# stepper_driver1_c.net
KiCad netlist of a schematic drawn in EAGLE
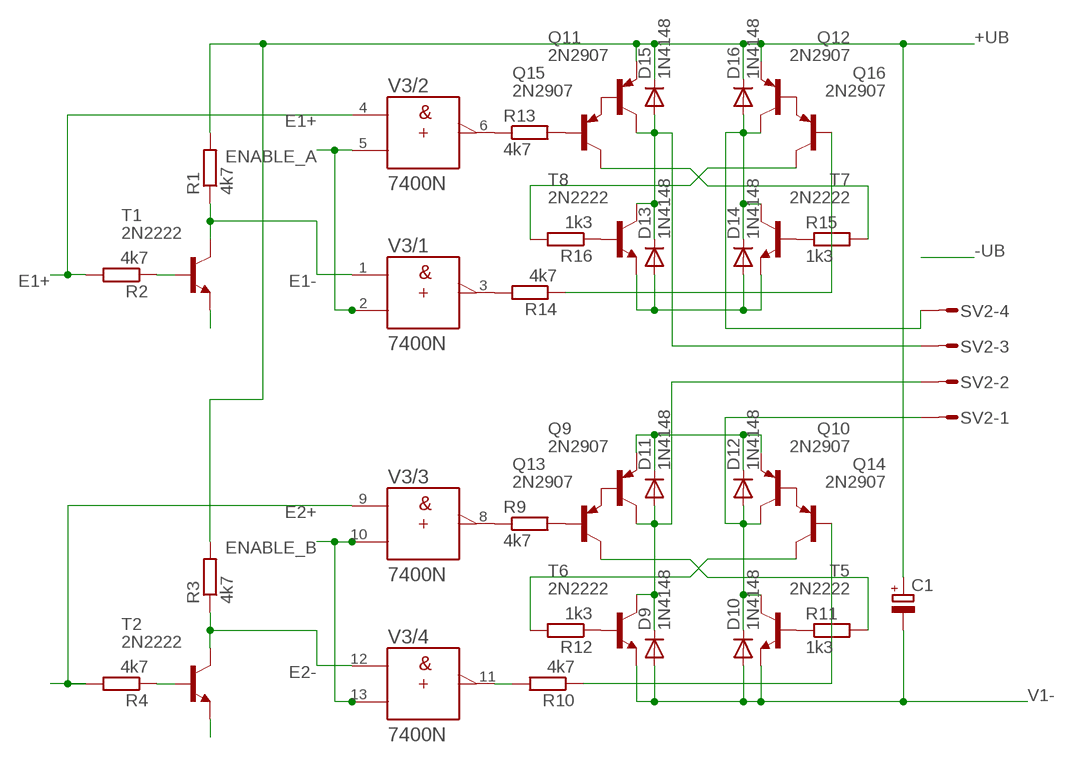
[diagram p0: schematic, sheet 1]

(export (version "E")
  (design (tool "Eeschema 10.0.6"))
  (components
    (comp (ref "C1")
      (value "CPOL-EUE3.5-10")
      (footprint "eagle-import:E3,5-10")
      (libsource (lib "eagle-import") (part "CPOL-EUE3.5-10"))
    )
    (comp (ref "D9")
      (value "1N4148")
      (footprint "eagle-import:D-2.5")
      (libsource (lib "eagle-import") (part "DIODE-D-2.5"))
    )
    (comp (ref "D10")
      (value "1N4148")
      (footprint "eagle-import:D-2.5")
      (libsource (lib "eagle-import") (part "DIODE-D-2.5"))
    )
    (comp (ref "D11")
      (value "1N4148")
      (footprint "eagle-import:D-2.5")
      (libsource (lib "eagle-import") (part "DIODE-D-2.5"))
    )
    (comp (ref "D12")
      (value "1N4148")
      (footprint "eagle-import:D-2.5")
      (libsource (lib "eagle-import") (part "DIODE-D-2.5"))
    )
    (comp (ref "D13")
      (value "1N4148")
      (footprint "eagle-import:D-2.5")
      (libsource (lib "eagle-import") (part "DIODE-D-2.5"))
    )
    (comp (ref "D14")
      (value "1N4148")
      (footprint "eagle-import:D-2.5")
      (libsource (lib "eagle-import") (part "DIODE-D-2.5"))
    )
    (comp (ref "D15")
      (value "1N4148")
      (footprint "eagle-import:D-2.5")
      (libsource (lib "eagle-import") (part "DIODE-D-2.5"))
    )
    (comp (ref "D16")
      (value "1N4148")
      (footprint "eagle-import:D-2.5")
      (libsource (lib "eagle-import") (part "DIODE-D-2.5"))
    )
    (comp (ref "Q9")
      (value "2N2907")
      (footprint "eagle-import:TO18")
      (libsource (lib "eagle-import") (part "2N2907"))
    )
    (comp (ref "Q10")
      (value "2N2907")
      (footprint "eagle-import:TO18")
      (libsource (lib "eagle-import") (part "2N2907"))
    )
    (comp (ref "Q11")
      (value "2N2907")
      (footprint "eagle-import:TO18")
      (libsource (lib "eagle-import") (part "2N2907"))
    )
    (comp (ref "Q12")
      (value "2N2907")
      (footprint "eagle-import:TO18")
      (libsource (lib "eagle-import") (part "2N2907"))
    )
    (comp (ref "Q13")
      (value "2N2907")
      (footprint "eagle-import:TO18")
      (libsource (lib "eagle-import") (part "2N2907"))
    )
    (comp (ref "Q14")
      (value "2N2907")
      (footprint "eagle-import:TO18")
      (libsource (lib "eagle-import") (part "2N2907"))
    )
    (comp (ref "Q15")
      (value "2N2907")
      (footprint "eagle-import:TO18")
      (libsource (lib "eagle-import") (part "2N2907"))
    )
    (comp (ref "Q16")
      (value "2N2907")
      (footprint "eagle-import:TO18")
      (libsource (lib "eagle-import") (part "2N2907"))
    )
    (comp (ref "R1")
      (value "4k7")
      (footprint "eagle-import:0207_10")
      (libsource (lib "eagle-import") (part "R-EU_0207/10"))
    )
    (comp (ref "R2")
      (value "4k7")
      (footprint "eagle-import:0207_10")
      (libsource (lib "eagle-import") (part "R-EU_0207/10"))
    )
    (comp (ref "R3")
      (value "4k7")
      (footprint "eagle-import:0207_10")
      (libsource (lib "eagle-import") (part "R-EU_0207/10"))
    )
    (comp (ref "R4")
      (value "4k7")
      (footprint "eagle-import:0207_10")
      (libsource (lib "eagle-import") (part "R-EU_0207/10"))
    )
    (comp (ref "R9")
      (value "4k7")
      (footprint "eagle-import:0207_10")
      (libsource (lib "eagle-import") (part "R-EU_0207/10"))
    )
    (comp (ref "R10")
      (value "4k7")
      (footprint "eagle-import:0207_12")
      (libsource (lib "eagle-import") (part "R-EU_0207/12"))
    )
    (comp (ref "R11")
      (value "1k3")
      (footprint "eagle-import:0207_10")
      (libsource (lib "eagle-import") (part "R-EU_0207/10"))
    )
    (comp (ref "R12")
      (value "1k3")
      (footprint "eagle-import:0207_10")
      (libsource (lib "eagle-import") (part "R-EU_0207/10"))
    )
    (comp (ref "R13")
      (value "4k7")
      (footprint "eagle-import:0207_10")
      (libsource (lib "eagle-import") (part "R-EU_0207/10"))
    )
    (comp (ref "R14")
      (value "4k7")
      (footprint "eagle-import:0207_10")
      (libsource (lib "eagle-import") (part "R-EU_0207/10"))
    )
    (comp (ref "R15")
      (value "1k3")
      (footprint "eagle-import:0207_10")
      (libsource (lib "eagle-import") (part "R-EU_0207/10"))
    )
    (comp (ref "R16")
      (value "1k3")
      (footprint "eagle-import:0207_10")
      (libsource (lib "eagle-import") (part "R-EU_0207/10"))
    )
    (comp (ref "SV2")
      (value "S04P")
      (footprint "eagle-import:S04P")
      (libsource (lib "eagle-import") (part "S04P"))
    )
    (comp (ref "T1")
      (value "2N2222")
      (footprint "eagle-import:TO18")
      (libsource (lib "eagle-import") (part "2N2222"))
    )
    (comp (ref "T2")
      (value "2N2222")
      (footprint "eagle-import:TO18")
      (libsource (lib "eagle-import") (part "2N2222"))
    )
    (comp (ref "T5")
      (value "2N2222")
      (footprint "eagle-import:TO18")
      (libsource (lib "eagle-import") (part "2N2222"))
    )
    (comp (ref "T6")
      (value "2N2222")
      (footprint "eagle-import:TO18")
      (libsource (lib "eagle-import") (part "2N2222"))
    )
    (comp (ref "T7")
      (value "2N2222")
      (footprint "eagle-import:TO18")
      (libsource (lib "eagle-import") (part "2N2222"))
    )
    (comp (ref "T8")
      (value "2N2222")
      (footprint "eagle-import:TO18")
      (libsource (lib "eagle-import") (part "2N2222"))
    )
    (comp (ref "V3")
      (value "7400N")
      (footprint "eagle-import:DIL14")
      (libsource (lib "eagle-import") (part "7400N"))
    )
  )
  (nets
    (net (code "1") (name "/+UB") (class "Default")
      (node (ref "C1") (pin "+") (pinfunction "+_+") (pintype "passive"))
      (node (ref "D11") (pin "C") (pinfunction "C_C") (pintype "passive"))
      (node (ref "D12") (pin "C") (pinfunction "C_C") (pintype "passive"))
      (node (ref "D15") (pin "C") (pinfunction "C_C") (pintype "passive"))
      (node (ref "D16") (pin "C") (pinfunction "C_C") (pintype "passive"))
      (node (ref "Q10") (pin "1") (pinfunction "E_1") (pintype "passive"))
      (node (ref "Q11") (pin "1") (pinfunction "E_1") (pintype "passive"))
      (node (ref "Q12") (pin "1") (pinfunction "E_1") (pintype "passive"))
      (node (ref "Q9") (pin "1") (pinfunction "E_1") (pintype "passive"))
      (node (ref "R1") (pin "2") (pinfunction "2_2") (pintype "passive"))
      (node (ref "R3") (pin "2") (pinfunction "2_2") (pintype "passive"))
    )
    (net (code "2") (name "/-UB") (class "Default")
      (node (ref "T1") (pin "1") (pinfunction "E_1") (pintype "passive"))
      (node (ref "T2") (pin "1") (pinfunction "E_1") (pintype "passive"))
    )
    (net (code "3") (name "/E1+") (class "Default")
      (node (ref "R2") (pin "2") (pinfunction "2_2") (pintype "passive"))
      (node (ref "V3") (pin "4") (pinfunction "A_4") (pintype "input"))
    )
    (net (code "4") (name "/E1-") (class "Default")
      (node (ref "R1") (pin "1") (pinfunction "1_1") (pintype "passive"))
      (node (ref "T1") (pin "3") (pinfunction "C_3") (pintype "passive"))
      (node (ref "V3") (pin "1") (pinfunction "A_1") (pintype "input"))
    )
    (net (code "5") (name "/E2+") (class "Default")
      (node (ref "R4") (pin "2") (pinfunction "2_2") (pintype "passive"))
      (node (ref "V3") (pin "9") (pinfunction "A_9") (pintype "input"))
    )
    (net (code "6") (name "/E2-") (class "Default")
      (node (ref "R3") (pin "1") (pinfunction "1_1") (pintype "passive"))
      (node (ref "T2") (pin "3") (pinfunction "C_3") (pintype "passive"))
      (node (ref "V3") (pin "12") (pinfunction "A_12") (pintype "input"))
    )
    (net (code "7") (name "/ENABLE_A") (class "Default")
      (node (ref "V3") (pin "2") (pinfunction "B_2") (pintype "input"))
      (node (ref "V3") (pin "5") (pinfunction "B_5") (pintype "input"))
    )
    (net (code "8") (name "/ENABLE_B") (class "Default")
      (node (ref "V3") (pin "10") (pinfunction "B_10") (pintype "input"))
      (node (ref "V3") (pin "13") (pinfunction "B_13") (pintype "input"))
    )
    (net (code "9") (name "/V1-") (class "Default")
      (node (ref "C1") (pin "-") (pinfunction "-_-") (pintype "passive"))
      (node (ref "D10") (pin "A") (pinfunction "A_A") (pintype "passive"))
      (node (ref "D13") (pin "A") (pinfunction "A_A") (pintype "passive"))
      (node (ref "D14") (pin "A") (pinfunction "A_A") (pintype "passive"))
      (node (ref "D9") (pin "A") (pinfunction "A_A") (pintype "passive"))
      (node (ref "T5") (pin "1") (pinfunction "E_1") (pintype "passive"))
      (node (ref "T6") (pin "1") (pinfunction "E_1") (pintype "passive"))
      (node (ref "T7") (pin "1") (pinfunction "E_1") (pintype "passive"))
      (node (ref "T8") (pin "1") (pinfunction "E_1") (pintype "passive"))
    )
    (net (code "10") (name "Net-(Q9-C)") (class "Default")
      (node (ref "D11") (pin "A") (pinfunction "A_A") (pintype "passive"))
      (node (ref "D9") (pin "C") (pinfunction "C_C") (pintype "passive"))
      (node (ref "Q9") (pin "3") (pinfunction "C_3") (pintype "passive"))
      (node (ref "SV2") (pin "2") (pinfunction "S_2") (pintype "passive"))
      (node (ref "T6") (pin "3") (pinfunction "C_3") (pintype "passive"))
    )
    (net (code "11") (name "Net-(Q10-B)") (class "Default")
      (node (ref "Q10") (pin "2") (pinfunction "B_2") (pintype "passive"))
      (node (ref "Q14") (pin "1") (pinfunction "E_1") (pintype "passive"))
    )
    (net (code "12") (name "Net-(Q10-C)") (class "Default")
      (node (ref "D10") (pin "C") (pinfunction "C_C") (pintype "passive"))
      (node (ref "D12") (pin "A") (pinfunction "A_A") (pintype "passive"))
      (node (ref "Q10") (pin "3") (pinfunction "C_3") (pintype "passive"))
      (node (ref "SV2") (pin "1") (pinfunction "S_1") (pintype "passive"))
      (node (ref "T5") (pin "3") (pinfunction "C_3") (pintype "passive"))
    )
    (net (code "13") (name "Net-(Q11-B)") (class "Default")
      (node (ref "Q11") (pin "2") (pinfunction "B_2") (pintype "passive"))
      (node (ref "Q15") (pin "1") (pinfunction "E_1") (pintype "passive"))
    )
    (net (code "14") (name "Net-(Q11-C)") (class "Default")
      (node (ref "D13") (pin "C") (pinfunction "C_C") (pintype "passive"))
      (node (ref "D15") (pin "A") (pinfunction "A_A") (pintype "passive"))
      (node (ref "Q11") (pin "3") (pinfunction "C_3") (pintype "passive"))
      (node (ref "SV2") (pin "3") (pinfunction "S_3") (pintype "passive"))
      (node (ref "T8") (pin "3") (pinfunction "C_3") (pintype "passive"))
    )
    (net (code "15") (name "Net-(Q12-B)") (class "Default")
      (node (ref "Q12") (pin "2") (pinfunction "B_2") (pintype "passive"))
      (node (ref "Q16") (pin "1") (pinfunction "E_1") (pintype "passive"))
    )
    (net (code "16") (name "Net-(Q12-C)") (class "Default")
      (node (ref "D14") (pin "C") (pinfunction "C_C") (pintype "passive"))
      (node (ref "D16") (pin "A") (pinfunction "A_A") (pintype "passive"))
      (node (ref "Q12") (pin "3") (pinfunction "C_3") (pintype "passive"))
      (node (ref "SV2") (pin "4") (pinfunction "S_4") (pintype "passive"))
      (node (ref "T7") (pin "3") (pinfunction "C_3") (pintype "passive"))
    )
    (net (code "17") (name "Net-(Q13-B)") (class "Default")
      (node (ref "Q13") (pin "2") (pinfunction "B_2") (pintype "passive"))
      (node (ref "R9") (pin "2") (pinfunction "2_2") (pintype "passive"))
    )
    (net (code "18") (name "Net-(Q13-C)") (class "Default")
      (node (ref "Q13") (pin "3") (pinfunction "C_3") (pintype "passive"))
      (node (ref "R11") (pin "2") (pinfunction "2_2") (pintype "passive"))
    )
    (net (code "19") (name "Net-(Q13-E)") (class "Default")
      (node (ref "Q13") (pin "1") (pinfunction "E_1") (pintype "passive"))
      (node (ref "Q9") (pin "2") (pinfunction "B_2") (pintype "passive"))
    )
    (net (code "20") (name "Net-(Q14-B)") (class "Default")
      (node (ref "Q14") (pin "2") (pinfunction "B_2") (pintype "passive"))
      (node (ref "R10") (pin "1") (pinfunction "1_1") (pintype "passive"))
    )
    (net (code "21") (name "Net-(Q14-C)") (class "Default")
      (node (ref "Q14") (pin "3") (pinfunction "C_3") (pintype "passive"))
      (node (ref "R12") (pin "2") (pinfunction "2_2") (pintype "passive"))
    )
    (net (code "22") (name "Net-(Q15-B)") (class "Default")
      (node (ref "Q15") (pin "2") (pinfunction "B_2") (pintype "passive"))
      (node (ref "R13") (pin "2") (pinfunction "2_2") (pintype "passive"))
    )
    (net (code "23") (name "Net-(Q15-C)") (class "Default")
      (node (ref "Q15") (pin "3") (pinfunction "C_3") (pintype "passive"))
      (node (ref "R15") (pin "2") (pinfunction "2_2") (pintype "passive"))
    )
    (net (code "24") (name "Net-(Q16-B)") (class "Default")
      (node (ref "Q16") (pin "2") (pinfunction "B_2") (pintype "passive"))
      (node (ref "R14") (pin "1") (pinfunction "1_1") (pintype "passive"))
    )
    (net (code "25") (name "Net-(Q16-C)") (class "Default")
      (node (ref "Q16") (pin "3") (pinfunction "C_3") (pintype "passive"))
      (node (ref "R16") (pin "2") (pinfunction "2_2") (pintype "passive"))
    )
    (net (code "26") (name "Net-(T1-B)") (class "Default")
      (node (ref "R2") (pin "1") (pinfunction "1_1") (pintype "passive"))
      (node (ref "T1") (pin "2") (pinfunction "B_2") (pintype "passive"))
    )
    (net (code "27") (name "Net-(T2-B)") (class "Default")
      (node (ref "R4") (pin "1") (pinfunction "1_1") (pintype "passive"))
      (node (ref "T2") (pin "2") (pinfunction "B_2") (pintype "passive"))
    )
    (net (code "28") (name "Net-(T5-B)") (class "Default")
      (node (ref "R11") (pin "1") (pinfunction "1_1") (pintype "passive"))
      (node (ref "T5") (pin "2") (pinfunction "B_2") (pintype "passive"))
    )
    (net (code "29") (name "Net-(T6-B)") (class "Default")
      (node (ref "R12") (pin "1") (pinfunction "1_1") (pintype "passive"))
      (node (ref "T6") (pin "2") (pinfunction "B_2") (pintype "passive"))
    )
    (net (code "30") (name "Net-(T7-B)") (class "Default")
      (node (ref "R15") (pin "1") (pinfunction "1_1") (pintype "passive"))
      (node (ref "T7") (pin "2") (pinfunction "B_2") (pintype "passive"))
    )
    (net (code "31") (name "Net-(T8-B)") (class "Default")
      (node (ref "R16") (pin "1") (pinfunction "1_1") (pintype "passive"))
      (node (ref "T8") (pin "2") (pinfunction "B_2") (pintype "passive"))
    )
    (net (code "32") (name "Net-(V3C-Y)") (class "Default")
      (node (ref "R14") (pin "2") (pinfunction "2_2") (pintype "passive"))
      (node (ref "V3") (pin "3") (pinfunction "Y_3") (pintype "output"))
    )
    (net (code "33") (name "Net-(V3D-Y)") (class "Default")
      (node (ref "R13") (pin "1") (pinfunction "1_1") (pintype "passive"))
      (node (ref "V3") (pin "6") (pinfunction "Y_6") (pintype "output"))
    )
    (net (code "34") (name "Net-(V3E-Y)") (class "Default")
      (node (ref "R9") (pin "1") (pinfunction "1_1") (pintype "passive"))
      (node (ref "V3") (pin "8") (pinfunction "Y_8") (pintype "output"))
    )
    (net (code "35") (name "Net-(V3F-Y)") (class "Default")
      (node (ref "R10") (pin "2") (pinfunction "2_2") (pintype "passive"))
      (node (ref "V3") (pin "11") (pinfunction "Y_11") (pintype "output"))
    )
  )
)
